# 1_V3.net
KiCad netlist of a schematic drawn in Altium Designer
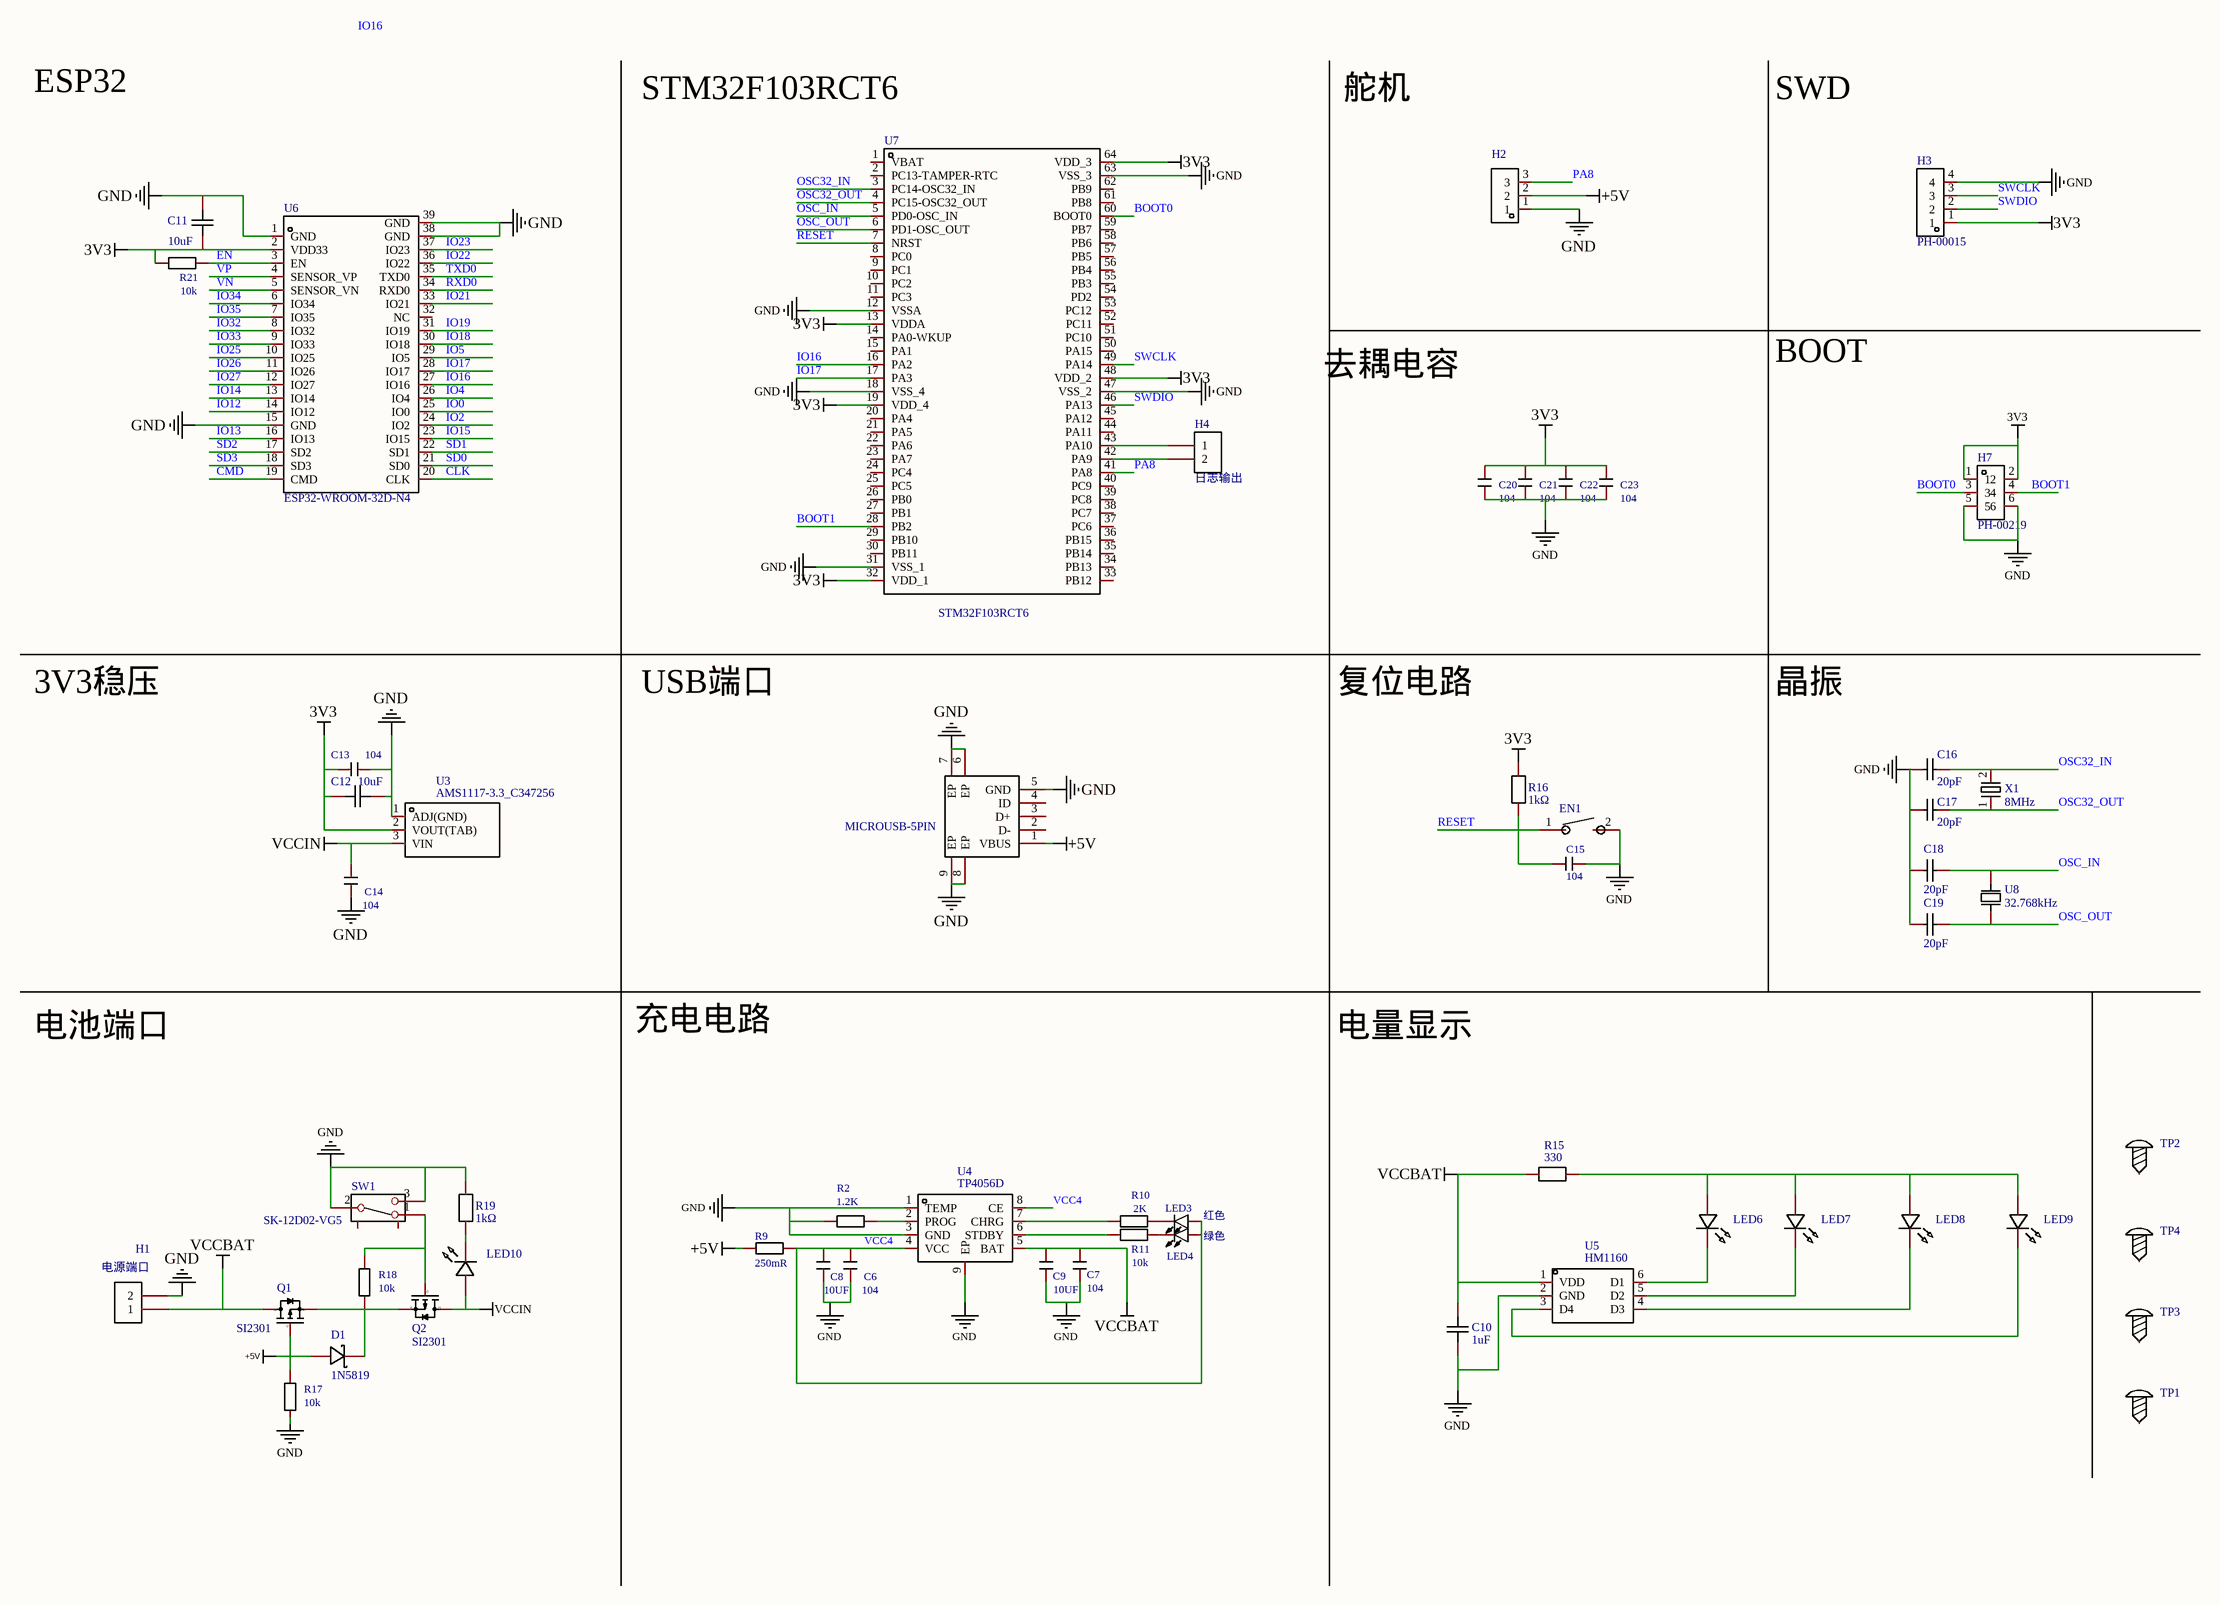
[diagram p0: 1_V3.schdoc]

(export (version "E")
  (design (tool "Eeschema 10.0.6"))
  (components
    (comp (ref "C6")
      (value "104")
      (fields (field (name "NAME") "104") (field (name "版权归属") "源创客"))
      (libsource (lib "altium-import") (part "root_1_104_"))
    )
    (comp (ref "C7")
      (value "104")
      (fields (field (name "NAME") "104") (field (name "版权归属") "源创客"))
      (libsource (lib "altium-import") (part "root_1_104_"))
    )
    (comp (ref "C8")
      (value "10UF")
      (fields (field (name "NAME") "10UF") (field (name "版权归属") "源创客"))
      (libsource (lib "altium-import") (part "root_1_10UF_"))
    )
    (comp (ref "C9")
      (value "10UF")
      (fields (field (name "NAME") "10UF") (field (name "版权归属") "源创客"))
      (libsource (lib "altium-import") (part "root_1_10UF_"))
    )
    (comp (ref "C10")
      (value "1uF")
      (fields (field (name "NAME") "1uF"))
      (libsource (lib "altium-import") (part "root_1_1uF_"))
    )
    (comp (ref "C11")
      (value "10uF")
      (fields (field (name "NAME") "10uF"))
      (libsource (lib "altium-import") (part "root_1_10uF_"))
    )
    (comp (ref "C12")
      (value "10uF")
      (fields (field (name "NAME") "10uF"))
      (libsource (lib "altium-import") (part "root_0_10uF_"))
    )
    (comp (ref "C13")
      (value "104")
      (fields (field (name "NAME") "104") (field (name "版权归属") "源创客"))
      (libsource (lib "altium-import") (part "root_2_104_"))
    )
    (comp (ref "C14")
      (value "104")
      (fields (field (name "NAME") "104") (field (name "版权归属") "源创客"))
      (libsource (lib "altium-import") (part "root_1_104_"))
    )
    (comp (ref "C15")
      (value "104")
      (fields (field (name "NAME") "104") (field (name "版权归属") "源创客"))
      (libsource (lib "altium-import") (part "root_2_104_"))
    )
    (comp (ref "C16")
      (value "20pF")
      (description "温度系数:C0G;容值:20pF;精度:±5%;额定电压:50V;")
      (fields
        (field (name "NAME") "20pF")
        (field (name "MANUFACTURER") "SAMSUNG(三星)")
        (field (name "MANUFACTURER PART") "CL10C200JB8NNNC")
      )
      (libsource (lib "altium-import") (part "root_2_CL10C200JB8NNNC_"))
    )
    (comp (ref "C17")
      (value "20pF")
      (description "温度系数:C0G;容值:20pF;精度:±5%;额定电压:50V;")
      (fields
        (field (name "NAME") "20pF")
        (field (name "MANUFACTURER") "SAMSUNG(三星)")
        (field (name "MANUFACTURER PART") "CL10C200JB8NNNC")
      )
      (libsource (lib "altium-import") (part "root_2_CL10C200JB8NNNC_"))
    )
    (comp (ref "C18")
      (value "20pF")
      (description "温度系数:C0G;容值:20pF;精度:±5%;额定电压:50V;")
      (fields
        (field (name "NAME") "20pF")
        (field (name "MANUFACTURER") "SAMSUNG(三星)")
        (field (name "MANUFACTURER PART") "CL10C200JB8NNNC")
      )
      (libsource (lib "altium-import") (part "root_2_CL10C200JB8NNNC_"))
    )
    (comp (ref "C19")
      (value "20pF")
      (description "温度系数:C0G;容值:20pF;精度:±5%;额定电压:50V;")
      (fields
        (field (name "NAME") "20pF")
        (field (name "MANUFACTURER") "SAMSUNG(三星)")
        (field (name "MANUFACTURER PART") "CL10C200JB8NNNC")
      )
      (libsource (lib "altium-import") (part "root_2_CL10C200JB8NNNC_"))
    )
    (comp (ref "C20")
      (value "104")
      (fields (field (name "NAME") "104") (field (name "版权归属") "源创客"))
      (libsource (lib "altium-import") (part "root_3_104_"))
    )
    (comp (ref "C21")
      (value "104")
      (fields (field (name "NAME") "104") (field (name "版权归属") "源创客"))
      (libsource (lib "altium-import") (part "root_3_104_"))
    )
    (comp (ref "C22")
      (value "104")
      (fields (field (name "NAME") "104") (field (name "版权归属") "源创客"))
      (libsource (lib "altium-import") (part "root_3_104_"))
    )
    (comp (ref "C23")
      (value "104")
      (fields (field (name "NAME") "104") (field (name "版权归属") "源创客"))
      (libsource (lib "altium-import") (part "root_3_104_"))
    )
    (comp (ref "D1")
      (value "1N5819")
      (description "直流反向耐压(Vr):40V;平均整流电流(Io):1A;正向压降(Vf):500mV@1A;")
      (fields (field (name "NAME") "1N5819") (field (name "MANUFACTURER") "KEXIN(科信)"))
      (libsource (lib "altium-import") (part "root_2_1N5819_C437199_"))
    )
    (comp (ref "EN1")
      (value "TSA343G00-250J2")
      (fields (field (name "MANUFACTURER") "BRIGHT(博瑞泰)"))
      (libsource (lib "altium-import") (part "root_0_TSA343G00-250J2_"))
    )
    (comp (ref "H1")
      (value "电源端口")
      (fields
        (field (name "NAME") "电源端口")
        (field (name "MANUFACTURER") "TE Connectivity(美国泰科)")
        (field (name "MANUFACTURER PART") "3-644456-2")
      )
      (libsource (lib "altium-import") (part "root_2_电源端口_"))
    )
    (comp (ref "H2")
      (value "Z-211-0311-0021-001")
      (fields (field (name "MANUFACTURER") "Nextron(正凌)"))
      (libsource (lib "altium-import") (part "root_2_Z-211-0311-0021-001_"))
    )
    (comp (ref "H3")
      (value "PH-00015")
      (fields (field (name "NAME") "PH-00015") (field (name "MANUFACTURER") "Liansheng(连盛)"))
      (libsource (lib "altium-import") (part "root_2_PH-00015_"))
    )
    (comp (ref "H4")
      (value "日志输出")
      (fields
        (field (name "NAME") "日志输出")
        (field (name "MANUFACTURER") "TE Connectivity(美国泰科)")
        (field (name "MANUFACTURER PART") "3-644456-2")
      )
      (libsource (lib "altium-import") (part "root_0_电源端口_"))
    )
    (comp (ref "H7")
      (value "PH-00219")
      (fields (field (name "NAME") "PH-00219") (field (name "MANUFACTURER") "Liansheng(连盛)"))
      (libsource (lib "altium-import") (part "root_0_PH-00219_"))
    )
    (comp (ref "LED3")
      (value "红色")
      (fields (field (name "NAME") "红色") (field (name "版权归属") "源创客"))
      (libsource (lib "altium-import") (part "root_3_红色_"))
    )
    (comp (ref "LED4")
      (value "绿色")
      (fields (field (name "NAME") "绿色") (field (name "版权归属") "源创客"))
      (libsource (lib "altium-import") (part "root_3_绿色_"))
    )
    (comp (ref "LED6")
      (value "LED-0603_R")
      (fields
        (field (name "MANUFACTURER") "EVERLIGHT(台湾亿光)")
        (field (name "MANUFACTURER PART") "19-217/R6C-AL1M2VY/3T")
      )
      (libsource (lib "altium-import") (part "root_3_LED-0603_R_"))
    )
    (comp (ref "LED7")
      (value "LED-0603_R")
      (fields
        (field (name "MANUFACTURER") "EVERLIGHT(台湾亿光)")
        (field (name "MANUFACTURER PART") "19-217/R6C-AL1M2VY/3T")
      )
      (libsource (lib "altium-import") (part "root_3_LED-0603_R_"))
    )
    (comp (ref "LED8")
      (value "LED-0603_R")
      (fields
        (field (name "MANUFACTURER") "EVERLIGHT(台湾亿光)")
        (field (name "MANUFACTURER PART") "19-217/R6C-AL1M2VY/3T")
      )
      (libsource (lib "altium-import") (part "root_3_LED-0603_R_"))
    )
    (comp (ref "LED9")
      (value "LED-0603_R")
      (fields
        (field (name "MANUFACTURER") "EVERLIGHT(台湾亿光)")
        (field (name "MANUFACTURER PART") "19-217/R6C-AL1M2VY/3T")
      )
      (libsource (lib "altium-import") (part "root_3_LED-0603_R_"))
    )
    (comp (ref "LED10")
      (value "LED-0603_R")
      (fields
        (field (name "MANUFACTURER") "EVERLIGHT(台湾亿光)")
        (field (name "MANUFACTURER PART") "19-217/R6C-AL1M2VY/3T")
      )
      (libsource (lib "altium-import") (part "root_1_LED-0603_R_"))
    )
    (comp (ref "NO1")
      (value "MICROUSB-5PIN")
      (fields (field (name "NAME") "MICROUSB-5PIN") (field (name "MANUFACTURER PART") "MicroUSB-5PIN"))
      (libsource (lib "altium-import") (part "root_2_MICROUSB-5PIN_"))
    )
    (comp (ref "Q1")
      (value "SI2301")
      (fields (field (name "NAME") "SI2301") (field (name "MANUFACTURER") "Hottech(合科泰)"))
      (libsource (lib "altium-import") (part "root_1_SI2301_C181086_"))
    )
    (comp (ref "Q2")
      (value "SI2301")
      (fields (field (name "NAME") "SI2301") (field (name "MANUFACTURER") "Hottech(合科泰)"))
      (libsource (lib "altium-import") (part "root_3_SI2301_C181086_"))
    )
    (comp (ref "R2")
      (value "1.2K")
      (fields (field (name "NAME") "1.2K") (field (name "版权归属") "源创客"))
      (libsource (lib "altium-import") (part "root_0_1K_"))
    )
    (comp (ref "R9")
      (value "250mR")
      (fields (field (name "NAME") "250mR") (field (name "版权归属") "源创客"))
      (libsource (lib "altium-import") (part "root_0_250mR_"))
    )
    (comp (ref "R10")
      (value "2K")
      (fields (field (name "NAME") "2K") (field (name "版权归属") "源创客"))
      (libsource (lib "altium-import") (part "root_0_2K_"))
    )
    (comp (ref "R11")
      (value "10k")
      (fields (field (name "NAME") "10k") (field (name "版权归属") "源创客"))
      (libsource (lib "altium-import") (part "root_0_10k_"))
    )
    (comp (ref "R15")
      (value "330")
      (fields (field (name "NAME") "330"))
      (libsource (lib "altium-import") (part "root_0_330_"))
    )
    (comp (ref "R16")
      (value "1kΩ")
      (fields
        (field (name "NAME") "1kΩ")
        (field (name "MANUFACTURER") "PANASONIC(松下)")
        (field (name "MANUFACTURER PART") "ERA3VEB1001V")
        (field (name "TOLERANCE") "±0.1%")
      )
      (libsource (lib "altium-import") (part "root_3_ERA3VEB1001V_"))
    )
    (comp (ref "R17")
      (value "10k")
      (fields (field (name "NAME") "10k") (field (name "版权归属") "源创客"))
      (libsource (lib "altium-import") (part "root_1_10k_"))
    )
    (comp (ref "R18")
      (value "10k")
      (fields (field (name "NAME") "10k") (field (name "版权归属") "源创客"))
      (libsource (lib "altium-import") (part "root_1_10k_"))
    )
    (comp (ref "R19")
      (value "1kΩ")
      (fields
        (field (name "NAME") "1kΩ")
        (field (name "MANUFACTURER") "PANASONIC(松下)")
        (field (name "MANUFACTURER PART") "ERA3VEB1001V")
        (field (name "TOLERANCE") "±0.1%")
      )
      (libsource (lib "altium-import") (part "root_3_ERA3VEB1001V_"))
    )
    (comp (ref "R21")
      (value "10k")
      (fields (field (name "NAME") "10k") (field (name "版权归属") "源创客"))
      (libsource (lib "altium-import") (part "root_0_10k_"))
    )
    (comp (ref "SW1")
      (value "SK-12D02-VG5")
      (fields (field (name "NAME") "SK-12D02-VG5") (field (name "MANUFACTURER") "韩国韩荣"))
      (libsource (lib "altium-import") (part "root_0_SK-12D02-VG5_C136722_"))
    )
    (comp (ref "TP1") (value "M2螺丝") (libsource (lib "altium-import") (part "root_0_M2螺丝_")))
    (comp (ref "TP2") (value "M2螺丝") (libsource (lib "altium-import") (part "root_0_M2螺丝_")))
    (comp (ref "TP3") (value "M2螺丝") (libsource (lib "altium-import") (part "root_0_M2螺丝_")))
    (comp (ref "TP4") (value "M2螺丝") (libsource (lib "altium-import") (part "root_0_M2螺丝_")))
    (comp (ref "U3")
      (value "AMS1117-3.3_C347256")
      (fields
        (field (name "NAME") "AMS1117-3.3_C347256")
        (field (name "MANUFACTURER") "Youtai Semiconductor Co., Ltd.")
        (field (name "MANUFACTURER PART") "AMS1117-3.3")
      )
      (libsource (lib "altium-import") (part "root_0_AMS1117-3.3_C347256_"))
    )
    (comp (ref "U4")
      (value "TP4056D")
      (fields (field (name "NAME") "TP4056D") (field (name "MANUFACTURER") "拓微集成"))
      (libsource (lib "altium-import") (part "root_0_TP4056D_"))
    )
    (comp (ref "U5")
      (value "HM1160")
      (fields
        (field (name "NAME") "HM1160")
        (field (name "MANUFACTURER") "Shenzhen Chip Hope Micro-Electronics")
        (field (name "MANUFACTURER PART") "LP3772-1")
      )
      (libsource (lib "altium-import") (part "root_0_HM1160_"))
    )
    (comp (ref "U6")
      (value "ESP32-WROOM-32D-N4")
      (description "ESP32-WROOM-32D 集成 ESP32-D0WD，功能强大，用途广泛，可以用于低功耗传感器网络和要求极高的任务，例如语音编码、音频流和 MP3 解码等。")
      (fields (field (name "NAME") "ESP32-WROOM-32D-N4") (field (name "MANUFACTURER") "ESPRESSIF(乐鑫)"))
      (libsource (lib "altium-import") (part "root_0_ESP32-WROOM-32D-N4_C473012_"))
    )
    (comp (ref "U7")
      (value "STM32F103RCT6")
      (description "工作电压:2V ~ 3.6V;主频（MAX):72MHz;")
      (fields (field (name "NAME") "STM32F103RCT6") (field (name "MANUFACTURER") "ST(意法半导体)"))
      (libsource (lib "altium-import") (part "root_0_STM32F103RCT6_"))
    )
    (comp (ref "U8")
      (value "32.768kHz")
      (description "晶振类型:贴片无源晶振;频率:32.768kHz;频率公差:±20ppm;负载电容:12.5pF;工作温度:-40℃~+125℃;")
      (fields
        (field (name "NAME") "32.768kHz")
        (field (name "MANUFACTURER") "EPSON(爱普生)")
        (field (name "MANUFACTURER PART") "X1A0000910001")
      )
      (libsource (lib "altium-import") (part "root_1_X1A0000910001_"))
    )
    (comp (ref "X1")
      (value "8MHz")
      (description "晶振类型:49S晶振;频率:8MHz;频率公差:±30ppm;频率稳定度:±50ppm;负载电容:20pF;等效串联电阻(ESR):60Ω;工作温度:-40℃~+85℃;")
      (fields
        (field (name "NAME") "8MHz")
        (field (name "MANUFACTURER") "HCI(杭晶)")
        (field (name "MANUFACTURER PART") "X49ST2-8.000-F20JGDT")
      )
      (libsource (lib "altium-import") (part "root_1_X49ST2-8.000-F20JGDT_"))
    )
  )
  (nets
    (net (code "1") (name "+5V") (class "Default")
      (node (ref "D1") (pin "2") (pinfunction "A_2") (pintype "passive"))
      (node (ref "H2") (pin "2") (pinfunction "2_2") (pintype "passive"))
      (node (ref "NO1") (pin "1") (pinfunction "VBUS_1") (pintype "passive"))
      (node (ref "Q1") (pin "1") (pinfunction "G_1") (pintype "passive"))
      (node (ref "R17") (pin "2") (pinfunction "2_2") (pintype "passive"))
      (node (ref "R9") (pin "1") (pinfunction "1_1") (pintype "passive"))
    )
    (net (code "2") (name "/BOOT0") (class "Default")
      (node (ref "H7") (pin "3") (pinfunction "3_3") (pintype "passive"))
      (node (ref "U7") (pin "60") (pinfunction "BOOT0_60") (pintype "passive"))
    )
    (net (code "3") (name "/BOOT1") (class "Default")
      (node (ref "H7") (pin "4") (pinfunction "4_4") (pintype "passive"))
      (node (ref "U7") (pin "28") (pinfunction "PB2_28") (pintype "passive"))
    )
    (net (code "4") (name "/CLK") (class "Default")
      (node (ref "U6") (pin "20") (pinfunction "CLK_20") (pintype "passive"))
    )
    (net (code "5") (name "/CMD") (class "Default")
      (node (ref "U6") (pin "19") (pinfunction "CMD_19") (pintype "passive"))
    )
    (net (code "6") (name "/EN") (class "Default")
      (node (ref "R21") (pin "2") (pinfunction "2_2") (pintype "passive"))
      (node (ref "U6") (pin "3") (pinfunction "EN_3") (pintype "passive"))
    )
    (net (code "7") (name "/IO0") (class "Default")
      (node (ref "U6") (pin "25") (pinfunction "IO0_25") (pintype "passive"))
    )
    (net (code "8") (name "/IO2") (class "Default")
      (node (ref "U6") (pin "24") (pinfunction "IO2_24") (pintype "passive"))
    )
    (net (code "9") (name "/IO4") (class "Default")
      (node (ref "U6") (pin "26") (pinfunction "IO4_26") (pintype "passive"))
    )
    (net (code "10") (name "/IO5") (class "Default")
      (node (ref "U6") (pin "29") (pinfunction "IO5_29") (pintype "passive"))
    )
    (net (code "11") (name "/IO12") (class "Default")
      (node (ref "U6") (pin "14") (pinfunction "IO12_14") (pintype "passive"))
    )
    (net (code "12") (name "/IO13") (class "Default")
      (node (ref "U6") (pin "16") (pinfunction "IO13_16") (pintype "passive"))
    )
    (net (code "13") (name "/IO14") (class "Default")
      (node (ref "U6") (pin "13") (pinfunction "IO14_13") (pintype "passive"))
    )
    (net (code "14") (name "/IO15") (class "Default")
      (node (ref "U6") (pin "23") (pinfunction "IO15_23") (pintype "passive"))
    )
    (net (code "15") (name "/IO16") (class "Default")
      (node (ref "U6") (pin "27") (pinfunction "IO16_27") (pintype "passive"))
      (node (ref "U7") (pin "16") (pinfunction "PA2_16") (pintype "passive"))
    )
    (net (code "16") (name "/IO17") (class "Default")
      (node (ref "U6") (pin "28") (pinfunction "IO17_28") (pintype "passive"))
      (node (ref "U7") (pin "17") (pinfunction "PA3_17") (pintype "passive"))
    )
    (net (code "17") (name "/IO18") (class "Default")
      (node (ref "U6") (pin "30") (pinfunction "IO18_30") (pintype "passive"))
    )
    (net (code "18") (name "/IO19") (class "Default")
      (node (ref "U6") (pin "31") (pinfunction "IO19_31") (pintype "passive"))
    )
    (net (code "19") (name "/IO21") (class "Default")
      (node (ref "U6") (pin "33") (pinfunction "IO21_33") (pintype "passive"))
    )
    (net (code "20") (name "/IO22") (class "Default")
      (node (ref "U6") (pin "36") (pinfunction "IO22_36") (pintype "passive"))
    )
    (net (code "21") (name "/IO23") (class "Default")
      (node (ref "U6") (pin "37") (pinfunction "IO23_37") (pintype "passive"))
    )
    (net (code "22") (name "/IO25") (class "Default")
      (node (ref "U6") (pin "10") (pinfunction "IO25_10") (pintype "passive"))
    )
    (net (code "23") (name "/IO26") (class "Default")
      (node (ref "U6") (pin "11") (pinfunction "IO26_11") (pintype "passive"))
    )
    (net (code "24") (name "/IO27") (class "Default")
      (node (ref "U6") (pin "12") (pinfunction "IO27_12") (pintype "passive"))
    )
    (net (code "25") (name "/IO32") (class "Default")
      (node (ref "U6") (pin "8") (pinfunction "IO32_8") (pintype "passive"))
    )
    (net (code "26") (name "/IO33") (class "Default")
      (node (ref "U6") (pin "9") (pinfunction "IO33_9") (pintype "passive"))
    )
    (net (code "27") (name "/IO34") (class "Default")
      (node (ref "U6") (pin "6") (pinfunction "IO34_6") (pintype "passive"))
    )
    (net (code "28") (name "/IO35") (class "Default")
      (node (ref "U6") (pin "7") (pinfunction "IO35_7") (pintype "passive"))
    )
    (net (code "29") (name "/OSC32_IN") (class "Default")
      (node (ref "C16") (pin "1") (pinfunction "1_1") (pintype "passive"))
      (node (ref "U7") (pin "3") (pinfunction "PC14-OSC32_IN_3") (pintype "passive"))
      (node (ref "X1") (pin "2") (pinfunction "GND_2") (pintype "passive"))
    )
    (net (code "30") (name "/OSC32_OUT") (class "Default")
      (node (ref "C17") (pin "1") (pinfunction "1_1") (pintype "passive"))
      (node (ref "U7") (pin "4") (pinfunction "PC15-OSC32_OUT_4") (pintype "passive"))
      (node (ref "X1") (pin "1") (pinfunction "1_1") (pintype "passive"))
    )
    (net (code "31") (name "/OSC_IN") (class "Default")
      (node (ref "C18") (pin "1") (pinfunction "1_1") (pintype "passive"))
      (node (ref "U7") (pin "5") (pinfunction "PD0-OSC_IN_5") (pintype "passive"))
      (node (ref "U8") (pin "2") (pinfunction "OSC2_2") (pintype "passive"))
    )
    (net (code "32") (name "/OSC_OUT") (class "Default")
      (node (ref "C19") (pin "1") (pinfunction "1_1") (pintype "passive"))
      (node (ref "U7") (pin "6") (pinfunction "PD1-OSC_OUT_6") (pintype "passive"))
      (node (ref "U8") (pin "1") (pinfunction "OSC1_1") (pintype "passive"))
    )
    (net (code "33") (name "/PA8") (class "Default")
      (node (ref "H2") (pin "3") (pinfunction "3_3") (pintype "passive"))
      (node (ref "U7") (pin "41") (pinfunction "PA8_41") (pintype "passive"))
    )
    (net (code "34") (name "/RESET") (class "Default")
      (node (ref "C15") (pin "2") (pinfunction "2_2") (pintype "passive"))
      (node (ref "EN1") (pin "1") (pinfunction "1_1") (pintype "passive"))
      (node (ref "R16") (pin "2") (pinfunction "2_2") (pintype "passive"))
      (node (ref "U7") (pin "7") (pinfunction "NRST_7") (pintype "passive"))
    )
    (net (code "35") (name "/RXD0") (class "Default")
      (node (ref "U6") (pin "34") (pinfunction "RXD0_34") (pintype "passive"))
    )
    (net (code "36") (name "/SD0") (class "Default")
      (node (ref "U6") (pin "21") (pinfunction "SD0_21") (pintype "passive"))
    )
    (net (code "37") (name "/SD1") (class "Default")
      (node (ref "U6") (pin "22") (pinfunction "SD1_22") (pintype "passive"))
    )
    (net (code "38") (name "/SD2") (class "Default")
      (node (ref "U6") (pin "17") (pinfunction "SD2_17") (pintype "passive"))
    )
    (net (code "39") (name "/SD3") (class "Default")
      (node (ref "U6") (pin "18") (pinfunction "SD3_18") (pintype "passive"))
    )
    (net (code "40") (name "/SWCLK") (class "Default")
      (node (ref "H3") (pin "3") (pinfunction "3_3") (pintype "passive"))
      (node (ref "U7") (pin "49") (pinfunction "PA14_49") (pintype "passive"))
    )
    (net (code "41") (name "/SWDIO") (class "Default")
      (node (ref "H3") (pin "2") (pinfunction "2_2") (pintype "passive"))
      (node (ref "U7") (pin "46") (pinfunction "PA13_46") (pintype "passive"))
    )
    (net (code "42") (name "/TXD0") (class "Default")
      (node (ref "U6") (pin "35") (pinfunction "TXD0_35") (pintype "passive"))
    )
    (net (code "43") (name "/VCC4") (class "Default")
      (node (ref "C6") (pin "2") (pinfunction "2_2") (pintype "passive"))
      (node (ref "C8") (pin "2") (pinfunction "2_2") (pintype "passive"))
      (node (ref "LED3") (pin "1") (pinfunction "A_1") (pintype "passive"))
      (node (ref "LED4") (pin "1") (pinfunction "A_1") (pintype "passive"))
      (node (ref "R9") (pin "2") (pinfunction "2_2") (pintype "passive"))
      (node (ref "U4") (pin "4") (pinfunction "VCC_4") (pintype "passive"))
      (node (ref "U4") (pin "8") (pinfunction "CE_8") (pintype "passive"))
    )
    (net (code "44") (name "/VN") (class "Default")
      (node (ref "U6") (pin "5") (pinfunction "SENSOR_VN_5") (pintype "passive"))
    )
    (net (code "45") (name "/VP") (class "Default")
      (node (ref "U6") (pin "4") (pinfunction "SENSOR_VP_4") (pintype "passive"))
    )
    (net (code "46") (name "3V3") (class "Default")
      (node (ref "C11") (pin "1") (pinfunction "1_1") (pintype "passive"))
      (node (ref "C12") (pin "1") (pinfunction "1_1") (pintype "passive"))
      (node (ref "C13") (pin "2") (pinfunction "2_2") (pintype "passive"))
      (node (ref "C20") (pin "1") (pinfunction "1_1") (pintype "passive"))
      (node (ref "C21") (pin "1") (pinfunction "1_1") (pintype "passive"))
      (node (ref "C22") (pin "1") (pinfunction "1_1") (pintype "passive"))
      (node (ref "C23") (pin "1") (pinfunction "1_1") (pintype "passive"))
      (node (ref "H3") (pin "1") (pinfunction "1_1") (pintype "passive"))
      (node (ref "H7") (pin "1") (pinfunction "1_1") (pintype "passive"))
      (node (ref "H7") (pin "2") (pinfunction "2_2") (pintype "passive"))
      (node (ref "R16") (pin "1") (pinfunction "1_1") (pintype "passive"))
      (node (ref "R21") (pin "1") (pinfunction "1_1") (pintype "passive"))
      (node (ref "U3") (pin "2") (pinfunction "VOUT(TAB)_2") (pintype "passive"))
      (node (ref "U6") (pin "2") (pinfunction "VDD33_2") (pintype "passive"))
      (node (ref "U7") (pin "13") (pinfunction "VDDA_13") (pintype "passive"))
      (node (ref "U7") (pin "19") (pinfunction "VDD_4_19") (pintype "passive"))
      (node (ref "U7") (pin "32") (pinfunction "VDD_1_32") (pintype "passive"))
      (node (ref "U7") (pin "48") (pinfunction "VDD_2_48") (pintype "passive"))
      (node (ref "U7") (pin "64") (pinfunction "VDD_3_64") (pintype "passive"))
    )
    (net (code "47") (name "GND") (class "Default")
      (node (ref "C10") (pin "1") (pinfunction "1_1") (pintype "passive"))
      (node (ref "C11") (pin "2") (pinfunction "2_2") (pintype "passive"))
      (node (ref "C12") (pin "2") (pinfunction "2_2") (pintype "passive"))
      (node (ref "C13") (pin "1") (pinfunction "1_1") (pintype "passive"))
      (node (ref "C14") (pin "1") (pinfunction "1_1") (pintype "passive"))
      (node (ref "C15") (pin "1") (pinfunction "1_1") (pintype "passive"))
      (node (ref "C16") (pin "2") (pinfunction "2_2") (pintype "passive"))
      (node (ref "C17") (pin "2") (pinfunction "2_2") (pintype "passive"))
      (node (ref "C18") (pin "2") (pinfunction "2_2") (pintype "passive"))
      (node (ref "C19") (pin "2") (pinfunction "2_2") (pintype "passive"))
      (node (ref "C20") (pin "2") (pinfunction "2_2") (pintype "passive"))
      (node (ref "C21") (pin "2") (pinfunction "2_2") (pintype "passive"))
      (node (ref "C22") (pin "2") (pinfunction "2_2") (pintype "passive"))
      (node (ref "C23") (pin "2") (pinfunction "2_2") (pintype "passive"))
      (node (ref "C6") (pin "1") (pinfunction "1_1") (pintype "passive"))
      (node (ref "C7") (pin "1") (pinfunction "1_1") (pintype "passive"))
      (node (ref "C8") (pin "1") (pinfunction "1_1") (pintype "passive"))
      (node (ref "C9") (pin "1") (pinfunction "1_1") (pintype "passive"))
      (node (ref "EN1") (pin "2") (pinfunction "2_2") (pintype "passive"))
      (node (ref "H1") (pin "2") (pinfunction "2_2") (pintype "passive"))
      (node (ref "H2") (pin "1") (pinfunction "1_1") (pintype "passive"))
      (node (ref "H3") (pin "4") (pinfunction "4_4") (pintype "passive"))
      (node (ref "H7") (pin "5") (pinfunction "5_5") (pintype "passive"))
      (node (ref "H7") (pin "6") (pinfunction "6_6") (pintype "passive"))
      (node (ref "NO1") (pin "5") (pinfunction "GND_5") (pintype "passive"))
      (node (ref "NO1") (pin "6") (pinfunction "EP_6") (pintype "passive"))
      (node (ref "NO1") (pin "7") (pinfunction "EP_7") (pintype "passive"))
      (node (ref "NO1") (pin "8") (pinfunction "EP_8") (pintype "passive"))
      (node (ref "NO1") (pin "9") (pinfunction "EP_9") (pintype "passive"))
      (node (ref "R17") (pin "1") (pinfunction "1_1") (pintype "passive"))
      (node (ref "R19") (pin "1") (pinfunction "1_1") (pintype "passive"))
      (node (ref "R2") (pin "1") (pinfunction "1_1") (pintype "passive"))
      (node (ref "SW1") (pin "2") (pinfunction "2_2") (pintype "passive"))
      (node (ref "SW1") (pin "3") (pinfunction "3_3") (pintype "passive"))
      (node (ref "U3") (pin "1") (pinfunction "ADJ(GND)_1") (pintype "passive"))
      (node (ref "U4") (pin "1") (pinfunction "TEMP_1") (pintype "passive"))
      (node (ref "U4") (pin "3") (pinfunction "GND_3") (pintype "passive"))
      (node (ref "U4") (pin "9") (pinfunction "EP_9") (pintype "passive"))
      (node (ref "U5") (pin "2") (pinfunction "GND_2") (pintype "passive"))
      (node (ref "U6") (pin "1") (pinfunction "GND_1") (pintype "passive"))
      (node (ref "U6") (pin "15") (pinfunction "GND_15") (pintype "passive"))
      (node (ref "U6") (pin "38") (pinfunction "GND_38") (pintype "passive"))
      (node (ref "U6") (pin "39") (pinfunction "GND_39") (pintype "passive"))
      (node (ref "U7") (pin "12") (pinfunction "VSSA_12") (pintype "passive"))
      (node (ref "U7") (pin "18") (pinfunction "VSS_4_18") (pintype "passive"))
      (node (ref "U7") (pin "31") (pinfunction "VSS_1_31") (pintype "passive"))
      (node (ref "U7") (pin "47") (pinfunction "VSS_2_47") (pintype "passive"))
      (node (ref "U7") (pin "63") (pinfunction "VSS_3_63") (pintype "passive"))
    )
    (net (code "48") (name "Net-(D1-C)") (class "Default")
      (node (ref "D1") (pin "1") (pinfunction "C_1") (pintype "passive"))
      (node (ref "Q1") (pin "2") (pinfunction "S_2") (pintype "passive"))
      (node (ref "Q2") (pin "2") (pinfunction "S_2") (pintype "passive"))
      (node (ref "R18") (pin "1") (pinfunction "1_1") (pintype "passive"))
    )
    (net (code "49") (name "Net-(LED3-K)") (class "Default")
      (node (ref "LED3") (pin "2") (pinfunction "K_2") (pintype "passive"))
      (node (ref "R10") (pin "2") (pinfunction "2_2") (pintype "passive"))
    )
    (net (code "50") (name "Net-(LED4-K)") (class "Default")
      (node (ref "LED4") (pin "2") (pinfunction "K_2") (pintype "passive"))
      (node (ref "R11") (pin "2") (pinfunction "2_2") (pintype "passive"))
    )
    (net (code "51") (name "Net-(LED6-Pad1)") (class "Default")
      (node (ref "LED6") (pin "1") (pinfunction "1_1") (pintype "passive"))
      (node (ref "LED7") (pin "1") (pinfunction "1_1") (pintype "passive"))
      (node (ref "LED8") (pin "1") (pinfunction "1_1") (pintype "passive"))
      (node (ref "LED9") (pin "1") (pinfunction "1_1") (pintype "passive"))
      (node (ref "R15") (pin "2") (pinfunction "2_2") (pintype "passive"))
    )
    (net (code "52") (name "Net-(LED10-Pad2)") (class "Default")
      (node (ref "LED10") (pin "2") (pinfunction "2_2") (pintype "passive"))
      (node (ref "R19") (pin "2") (pinfunction "2_2") (pintype "passive"))
    )
    (net (code "53") (name "Net-(Q2-G)") (class "Default")
      (node (ref "Q2") (pin "1") (pinfunction "G_1") (pintype "passive"))
      (node (ref "R18") (pin "2") (pinfunction "2_2") (pintype "passive"))
      (node (ref "SW1") (pin "1") (pinfunction "1_1") (pintype "passive"))
    )
    (net (code "54") (name "Net-(U4-CHRG)") (class "Default")
      (node (ref "R10") (pin "1") (pinfunction "1_1") (pintype "passive"))
      (node (ref "U4") (pin "7") (pinfunction "CHRG_7") (pintype "passive"))
    )
    (net (code "55") (name "Net-(U4-PROG)") (class "Default")
      (node (ref "R2") (pin "2") (pinfunction "2_2") (pintype "passive"))
      (node (ref "U4") (pin "2") (pinfunction "PROG_2") (pintype "passive"))
    )
    (net (code "56") (name "Net-(U4-STDBY)") (class "Default")
      (node (ref "R11") (pin "1") (pinfunction "1_1") (pintype "passive"))
      (node (ref "U4") (pin "6") (pinfunction "STDBY_6") (pintype "passive"))
    )
    (net (code "57") (name "Net-(U5-D1)") (class "Default")
      (node (ref "LED6") (pin "2") (pinfunction "2_2") (pintype "passive"))
      (node (ref "U5") (pin "6") (pinfunction "D1_6") (pintype "passive"))
    )
    (net (code "58") (name "Net-(U5-D2)") (class "Default")
      (node (ref "LED7") (pin "2") (pinfunction "2_2") (pintype "passive"))
      (node (ref "U5") (pin "5") (pinfunction "D2_5") (pintype "passive"))
    )
    (net (code "59") (name "Net-(U5-D3)") (class "Default")
      (node (ref "LED8") (pin "2") (pinfunction "2_2") (pintype "passive"))
      (node (ref "U5") (pin "4") (pinfunction "D3_4") (pintype "passive"))
    )
    (net (code "60") (name "Net-(U5-D4)") (class "Default")
      (node (ref "LED9") (pin "2") (pinfunction "2_2") (pintype "passive"))
      (node (ref "U5") (pin "3") (pinfunction "D4_3") (pintype "passive"))
    )
    (net (code "61") (name "Net-(U7-PA9)") (class "Default")
      (node (ref "H4") (pin "2") (pinfunction "2_2") (pintype "passive"))
      (node (ref "U7") (pin "42") (pinfunction "PA9_42") (pintype "passive"))
    )
    (net (code "62") (name "Net-(U7-PA10)") (class "Default")
      (node (ref "H4") (pin "1") (pinfunction "1_1") (pintype "passive"))
      (node (ref "U7") (pin "43") (pinfunction "PA10_43") (pintype "passive"))
    )
    (net (code "63") (name "VCCBAT") (class "Default")
      (node (ref "C10") (pin "2") (pinfunction "2_2") (pintype "passive"))
      (node (ref "C7") (pin "2") (pinfunction "2_2") (pintype "passive"))
      (node (ref "C9") (pin "2") (pinfunction "2_2") (pintype "passive"))
      (node (ref "H1") (pin "1") (pinfunction "1_1") (pintype "passive"))
      (node (ref "Q1") (pin "3") (pinfunction "D_3") (pintype "passive"))
      (node (ref "R15") (pin "1") (pinfunction "1_1") (pintype "passive"))
      (node (ref "U4") (pin "5") (pinfunction "BAT_5") (pintype "passive"))
      (node (ref "U5") (pin "1") (pinfunction "VDD_1") (pintype "passive"))
    )
    (net (code "64") (name "VCCIN") (class "Default")
      (node (ref "C14") (pin "2") (pinfunction "2_2") (pintype "passive"))
      (node (ref "LED10") (pin "1") (pinfunction "1_1") (pintype "passive"))
      (node (ref "Q2") (pin "3") (pinfunction "D_3") (pintype "passive"))
      (node (ref "U3") (pin "3") (pinfunction "VIN_3") (pintype "passive"))
    )
    (net (code "65") (name "unconnected-(NO1-D+-Pad3)") (class "Default")
      (node (ref "NO1") (pin "3") (pinfunction "D+_3") (pintype "passive"))
    )
    (net (code "66") (name "unconnected-(NO1-D--Pad2)") (class "Default")
      (node (ref "NO1") (pin "2") (pinfunction "D-_2") (pintype "passive"))
    )
    (net (code "67") (name "unconnected-(NO1-ID-Pad4)") (class "Default")
      (node (ref "NO1") (pin "4") (pinfunction "ID_4") (pintype "passive"))
    )
    (net (code "68") (name "unconnected-(SW1-Pad4)") (class "Default")
      (node (ref "SW1") (pin "4") (pinfunction "4_4") (pintype "passive"))
    )
    (net (code "69") (name "unconnected-(SW1-Pad5)") (class "Default")
      (node (ref "SW1") (pin "5") (pinfunction "5_5") (pintype "passive"))
    )
    (net (code "70") (name "unconnected-(TP1-Pad1)") (class "Default")
      (node (ref "TP1") (pin "1") (pinfunction "1_1") (pintype "passive"))
    )
    (net (code "71") (name "unconnected-(TP2-Pad1)") (class "Default")
      (node (ref "TP2") (pin "1") (pinfunction "1_1") (pintype "passive"))
    )
    (net (code "72") (name "unconnected-(TP3-Pad1)") (class "Default")
      (node (ref "TP3") (pin "1") (pinfunction "1_1") (pintype "passive"))
    )
    (net (code "73") (name "unconnected-(TP4-Pad1)") (class "Default")
      (node (ref "TP4") (pin "1") (pinfunction "1_1") (pintype "passive"))
    )
    (net (code "74") (name "unconnected-(U6-NC-Pad32)") (class "Default")
      (node (ref "U6") (pin "32") (pinfunction "NC_32") (pintype "passive"))
    )
    (net (code "75") (name "unconnected-(U7-PA0-WKUP-Pad14)") (class "Default")
      (node (ref "U7") (pin "14") (pinfunction "PA0-WKUP_14") (pintype "passive"))
    )
    (net (code "76") (name "unconnected-(U7-PA1-Pad15)") (class "Default")
      (node (ref "U7") (pin "15") (pinfunction "PA1_15") (pintype "passive"))
    )
    (net (code "77") (name "unconnected-(U7-PA4-Pad20)") (class "Default")
      (node (ref "U7") (pin "20") (pinfunction "PA4_20") (pintype "passive"))
    )
    (net (code "78") (name "unconnected-(U7-PA5-Pad21)") (class "Default")
      (node (ref "U7") (pin "21") (pinfunction "PA5_21") (pintype "passive"))
    )
    (net (code "79") (name "unconnected-(U7-PA6-Pad22)") (class "Default")
      (node (ref "U7") (pin "22") (pinfunction "PA6_22") (pintype "passive"))
    )
    (net (code "80") (name "unconnected-(U7-PA7-Pad23)") (class "Default")
      (node (ref "U7") (pin "23") (pinfunction "PA7_23") (pintype "passive"))
    )
    (net (code "81") (name "unconnected-(U7-PA11-Pad44)") (class "Default")
      (node (ref "U7") (pin "44") (pinfunction "PA11_44") (pintype "passive"))
    )
    (net (code "82") (name "unconnected-(U7-PA12-Pad45)") (class "Default")
      (node (ref "U7") (pin "45") (pinfunction "PA12_45") (pintype "passive"))
    )
    (net (code "83") (name "unconnected-(U7-PA15-Pad50)") (class "Default")
      (node (ref "U7") (pin "50") (pinfunction "PA15_50") (pintype "passive"))
    )
    (net (code "84") (name "unconnected-(U7-PB0-Pad26)") (class "Default")
      (node (ref "U7") (pin "26") (pinfunction "PB0_26") (pintype "passive"))
    )
    (net (code "85") (name "unconnected-(U7-PB1-Pad27)") (class "Default")
      (node (ref "U7") (pin "27") (pinfunction "PB1_27") (pintype "passive"))
    )
    (net (code "86") (name "unconnected-(U7-PB3-Pad55)") (class "Default")
      (node (ref "U7") (pin "55") (pinfunction "PB3_55") (pintype "passive"))
    )
    (net (code "87") (name "unconnected-(U7-PB4-Pad56)") (class "Default")
      (node (ref "U7") (pin "56") (pinfunction "PB4_56") (pintype "passive"))
    )
    (net (code "88") (name "unconnected-(U7-PB5-Pad57)") (class "Default")
      (node (ref "U7") (pin "57") (pinfunction "PB5_57") (pintype "passive"))
    )
    (net (code "89") (name "unconnected-(U7-PB6-Pad58)") (class "Default")
      (node (ref "U7") (pin "58") (pinfunction "PB6_58") (pintype "passive"))
    )
    (net (code "90") (name "unconnected-(U7-PB7-Pad59)") (class "Default")
      (node (ref "U7") (pin "59") (pinfunction "PB7_59") (pintype "passive"))
    )
    (net (code "91") (name "unconnected-(U7-PB8-Pad61)") (class "Default")
      (node (ref "U7") (pin "61") (pinfunction "PB8_61") (pintype "passive"))
    )
    (net (code "92") (name "unconnected-(U7-PB9-Pad62)") (class "Default")
      (node (ref "U7") (pin "62") (pinfunction "PB9_62") (pintype "passive"))
    )
    (net (code "93") (name "unconnected-(U7-PB10-Pad29)") (class "Default")
      (node (ref "U7") (pin "29") (pinfunction "PB10_29") (pintype "passive"))
    )
    (net (code "94") (name "unconnected-(U7-PB11-Pad30)") (class "Default")
      (node (ref "U7") (pin "30") (pinfunction "PB11_30") (pintype "passive"))
    )
    (net (code "95") (name "unconnected-(U7-PB12-Pad33)") (class "Default")
      (node (ref "U7") (pin "33") (pinfunction "PB12_33") (pintype "passive"))
    )
    (net (code "96") (name "unconnected-(U7-PB13-Pad34)") (class "Default")
      (node (ref "U7") (pin "34") (pinfunction "PB13_34") (pintype "passive"))
    )
    (net (code "97") (name "unconnected-(U7-PB14-Pad35)") (class "Default")
      (node (ref "U7") (pin "35") (pinfunction "PB14_35") (pintype "passive"))
    )
    (net (code "98") (name "unconnected-(U7-PB15-Pad36)") (class "Default")
      (node (ref "U7") (pin "36") (pinfunction "PB15_36") (pintype "passive"))
    )
    (net (code "99") (name "unconnected-(U7-PC0-Pad8)") (class "Default")
      (node (ref "U7") (pin "8") (pinfunction "PC0_8") (pintype "passive"))
    )
    (net (code "100") (name "unconnected-(U7-PC1-Pad9)") (class "Default")
      (node (ref "U7") (pin "9") (pinfunction "PC1_9") (pintype "passive"))
    )
    (net (code "101") (name "unconnected-(U7-PC2-Pad10)") (class "Default")
      (node (ref "U7") (pin "10") (pinfunction "PC2_10") (pintype "passive"))
    )
    (net (code "102") (name "unconnected-(U7-PC3-Pad11)") (class "Default")
      (node (ref "U7") (pin "11") (pinfunction "PC3_11") (pintype "passive"))
    )
    (net (code "103") (name "unconnected-(U7-PC4-Pad24)") (class "Default")
      (node (ref "U7") (pin "24") (pinfunction "PC4_24") (pintype "passive"))
    )
    (net (code "104") (name "unconnected-(U7-PC5-Pad25)") (class "Default")
      (node (ref "U7") (pin "25") (pinfunction "PC5_25") (pintype "passive"))
    )
    (net (code "105") (name "unconnected-(U7-PC6-Pad37)") (class "Default")
      (node (ref "U7") (pin "37") (pinfunction "PC6_37") (pintype "passive"))
    )
    (net (code "106") (name "unconnected-(U7-PC7-Pad38)") (class "Default")
      (node (ref "U7") (pin "38") (pinfunction "PC7_38") (pintype "passive"))
    )
    (net (code "107") (name "unconnected-(U7-PC8-Pad39)") (class "Default")
      (node (ref "U7") (pin "39") (pinfunction "PC8_39") (pintype "passive"))
    )
    (net (code "108") (name "unconnected-(U7-PC9-Pad40)") (class "Default")
      (node (ref "U7") (pin "40") (pinfunction "PC9_40") (pintype "passive"))
    )
    (net (code "109") (name "unconnected-(U7-PC10-Pad51)") (class "Default")
      (node (ref "U7") (pin "51") (pinfunction "PC10_51") (pintype "passive"))
    )
    (net (code "110") (name "unconnected-(U7-PC11-Pad52)") (class "Default")
      (node (ref "U7") (pin "52") (pinfunction "PC11_52") (pintype "passive"))
    )
    (net (code "111") (name "unconnected-(U7-PC12-Pad53)") (class "Default")
      (node (ref "U7") (pin "53") (pinfunction "PC12_53") (pintype "passive"))
    )
    (net (code "112") (name "unconnected-(U7-PC13-TAMPER-RTC-Pad2)") (class "Default")
      (node (ref "U7") (pin "2") (pinfunction "PC13-TAMPER-RTC_2") (pintype "passive"))
    )
    (net (code "113") (name "unconnected-(U7-PD2-Pad54)") (class "Default")
      (node (ref "U7") (pin "54") (pinfunction "PD2_54") (pintype "passive"))
    )
    (net (code "114") (name "unconnected-(U7-VBAT-Pad1)") (class "Default")
      (node (ref "U7") (pin "1") (pinfunction "VBAT_1") (pintype "passive"))
    )
  )
)
